# Pneumatics.net
KiCad netlist of a schematic drawn in Altium Designer
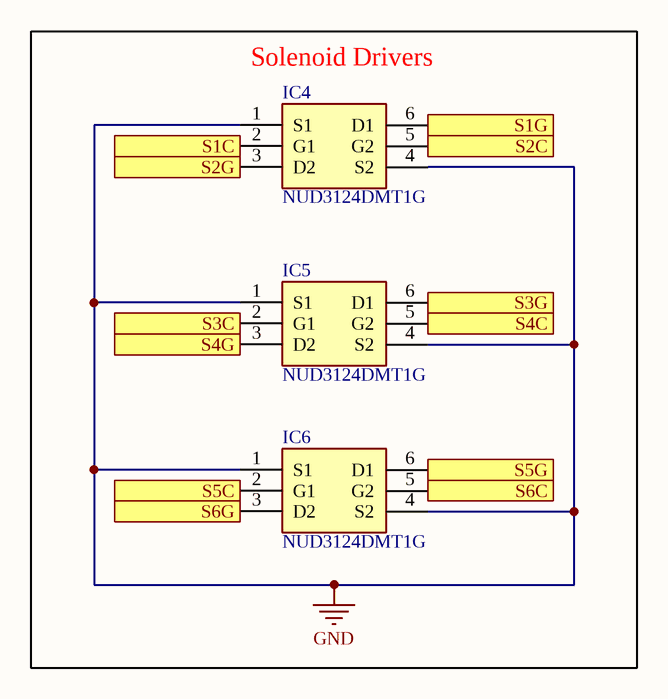
[diagram p0: Pneumatics.SchDoc]

(export (version "E")
  (design (tool "Eeschema 10.0.6"))
  (components
    (comp (ref "IC4")
      (value "NUD3124DMT1G")
      (footprint "SamacSys:SOT95P275X110-6N")
      (description "Integrated Circuit")
      (fields (field (name "MOUSER PART NUMBER") "863-NUD3124DMT1G"))
      (libsource (lib "*") (part "NUD3124DMT1G"))
    )
    (comp (ref "IC5")
      (value "NUD3124DMT1G")
      (footprint "SamacSys:SOT95P275X110-6N")
      (description "Integrated Circuit")
      (fields (field (name "MOUSER PART NUMBER") "863-NUD3124DMT1G"))
      (libsource (lib "*") (part "NUD3124DMT1G"))
    )
    (comp (ref "IC6")
      (value "NUD3124DMT1G")
      (footprint "SamacSys:SOT95P275X110-6N")
      (description "Integrated Circuit")
      (fields (field (name "MOUSER PART NUMBER") "863-NUD3124DMT1G"))
      (libsource (lib "*") (part "NUD3124DMT1G"))
    )
  )
  (nets
    (net (code "1") (name "/S1C") (class "Default")
      (node (ref "IC4") (pin "2") (pinfunction "G1_2") (pintype "passive"))
    )
    (net (code "2") (name "/S1G") (class "Default")
      (node (ref "IC4") (pin "6") (pinfunction "D1_6") (pintype "passive"))
    )
    (net (code "3") (name "/S2C") (class "Default")
      (node (ref "IC4") (pin "5") (pinfunction "G2_5") (pintype "passive"))
    )
    (net (code "4") (name "/S2G") (class "Default")
      (node (ref "IC4") (pin "3") (pinfunction "D2_3") (pintype "passive"))
    )
    (net (code "5") (name "/S3C") (class "Default")
      (node (ref "IC5") (pin "2") (pinfunction "G1_2") (pintype "passive"))
    )
    (net (code "6") (name "/S3G") (class "Default")
      (node (ref "IC5") (pin "6") (pinfunction "D1_6") (pintype "passive"))
    )
    (net (code "7") (name "/S4C") (class "Default")
      (node (ref "IC5") (pin "5") (pinfunction "G2_5") (pintype "passive"))
    )
    (net (code "8") (name "/S4G") (class "Default")
      (node (ref "IC5") (pin "3") (pinfunction "D2_3") (pintype "passive"))
    )
    (net (code "9") (name "/S5C") (class "Default")
      (node (ref "IC6") (pin "2") (pinfunction "G1_2") (pintype "passive"))
    )
    (net (code "10") (name "/S5G") (class "Default")
      (node (ref "IC6") (pin "6") (pinfunction "D1_6") (pintype "passive"))
    )
    (net (code "11") (name "/S6C") (class "Default")
      (node (ref "IC6") (pin "5") (pinfunction "G2_5") (pintype "passive"))
    )
    (net (code "12") (name "/S6G") (class "Default")
      (node (ref "IC6") (pin "3") (pinfunction "D2_3") (pintype "passive"))
    )
    (net (code "13") (name "GND") (class "Default")
      (node (ref "IC4") (pin "1") (pinfunction "S1_1") (pintype "passive"))
      (node (ref "IC4") (pin "4") (pinfunction "S2_4") (pintype "passive"))
      (node (ref "IC5") (pin "1") (pinfunction "S1_1") (pintype "passive"))
      (node (ref "IC5") (pin "4") (pinfunction "S2_4") (pintype "passive"))
      (node (ref "IC6") (pin "1") (pinfunction "S1_1") (pintype "passive"))
      (node (ref "IC6") (pin "4") (pinfunction "S2_4") (pintype "passive"))
    )
  )
)
